# ADC_Block.net
KiCad netlist of a schematic drawn in Altium Designer
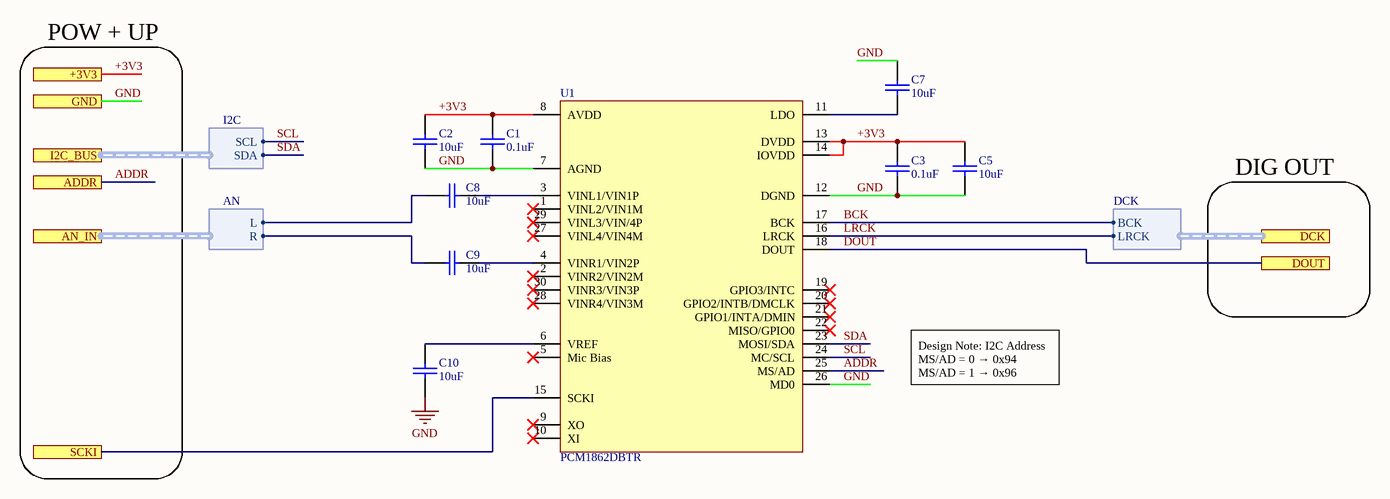
[diagram p0: ADC_Block.SchDoc]

(export (version "E")
  (design (tool "Eeschema 10.0.6"))
  (components
    (comp (ref "C1")
      (value "0.1uF")
      (footprint "0402-CAP-TDK")
      (fields (field (name "JLCPART") "C307331"))
      (libsource (lib "LIB2022 - Passives") (part "CAP-SMD"))
    )
    (comp (ref "C2")
      (value "10uF")
      (footprint "0603-CAP-TDK")
      (fields (field (name "JLCPART") "C96446"))
      (libsource (lib "LIB2022 - Passives") (part "CAP-SMD"))
    )
    (comp (ref "C3")
      (value "0.1uF")
      (footprint "0402-CAP-TDK")
      (fields (field (name "JLCPART") "C307331"))
      (libsource (lib "LIB2022 - Passives") (part "CAP-SMD"))
    )
    (comp (ref "C5")
      (value "10uF")
      (footprint "0603-CAP-TDK")
      (fields (field (name "JLCPART") "C96446"))
      (libsource (lib "LIB2022 - Passives") (part "CAP-SMD"))
    )
    (comp (ref "C7")
      (value "10uF")
      (footprint "0603-CAP-TDK")
      (fields (field (name "JLCPART") "C96446"))
      (libsource (lib "LIB2022 - Passives") (part "CAP-SMD"))
    )
    (comp (ref "C8")
      (value "10uF")
      (footprint "0603-CAP-TDK")
      (fields (field (name "JLCPART") "C96446"))
      (libsource (lib "LIB2022 - Passives") (part "CAP-SMD"))
    )
    (comp (ref "C9")
      (value "10uF")
      (footprint "0603-CAP-TDK")
      (fields (field (name "JLCPART") "C96446"))
      (libsource (lib "LIB2022 - Passives") (part "CAP-SMD"))
    )
    (comp (ref "C10")
      (value "10uF")
      (footprint "0603-CAP-TDK")
      (fields (field (name "JLCPART") "C96446"))
      (libsource (lib "LIB2022 - Passives") (part "CAP-SMD"))
    )
    (comp (ref "U1")
      (value "PCM1862DBTR")
      (footprint "TI-TSSOP-30-DBT0030A")
      (fields (field (name "JLCPART") "C544647"))
      (libsource (lib "LIB2022 - ICs") (part "PCM1862DBTR"))
    )
  )
  (nets
    (net (code "4") (name "/+3V3") (class "Default")
      (node (ref "C1") (pin "2") (pinfunction "2_2") (pintype "passive"))
      (node (ref "C2") (pin "2") (pinfunction "2_2") (pintype "passive"))
      (node (ref "C3") (pin "2") (pinfunction "2_2") (pintype "passive"))
      (node (ref "C5") (pin "2") (pinfunction "2_2") (pintype "passive"))
      (node (ref "U1") (pin "13") (pinfunction "DVDD_13") (pintype "passive"))
      (node (ref "U1") (pin "14") (pinfunction "IOVDD_14") (pintype "passive"))
      (node (ref "U1") (pin "8") (pinfunction "AVDD_8") (pintype "passive"))
    )
    (net (code "5") (name "/ADDR") (class "Default")
      (node (ref "U1") (pin "25") (pinfunction "MS/AD_25") (pintype "passive"))
    )
    (net (code "6") (name "/BCK") (class "Default")
      (node (ref "U1") (pin "17") (pinfunction "BCK_17") (pintype "passive"))
    )
    (net (code "7") (name "/DOUT") (class "Default")
      (node (ref "U1") (pin "18") (pinfunction "DOUT_18") (pintype "passive"))
    )
    (net (code "8") (name "/L") (class "Default")
      (node (ref "C8") (pin "2") (pinfunction "2_2") (pintype "passive"))
    )
    (net (code "9") (name "/LRCK") (class "Default")
      (node (ref "U1") (pin "16") (pinfunction "LRCK_16") (pintype "passive"))
    )
    (net (code "10") (name "/R") (class "Default")
      (node (ref "C9") (pin "2") (pinfunction "2_2") (pintype "passive"))
    )
    (net (code "11") (name "/SCKI") (class "Default")
      (node (ref "U1") (pin "15") (pinfunction "SCKI_15") (pintype "passive"))
    )
    (net (code "12") (name "/SCL") (class "Default")
      (node (ref "U1") (pin "24") (pinfunction "MC/SCL_24") (pintype "passive"))
    )
    (net (code "13") (name "/SDA") (class "Default")
      (node (ref "U1") (pin "23") (pinfunction "MOSI/SDA_23") (pintype "passive"))
    )
    (net (code "17") (name "GND") (class "Default")
      (node (ref "C1") (pin "1") (pinfunction "1_1") (pintype "passive"))
      (node (ref "C10") (pin "1") (pinfunction "1_1") (pintype "passive"))
      (node (ref "C2") (pin "1") (pinfunction "1_1") (pintype "passive"))
      (node (ref "C3") (pin "1") (pinfunction "1_1") (pintype "passive"))
      (node (ref "C5") (pin "1") (pinfunction "1_1") (pintype "passive"))
      (node (ref "C7") (pin "2") (pinfunction "2_2") (pintype "passive"))
      (node (ref "U1") (pin "12") (pinfunction "DGND_12") (pintype "passive"))
      (node (ref "U1") (pin "26") (pinfunction "MD0_26") (pintype "passive"))
      (node (ref "U1") (pin "7") (pinfunction "AGND_7") (pintype "passive"))
    )
    (net (code "18") (name "Net-(U1-LDO)") (class "Default")
      (node (ref "C7") (pin "1") (pinfunction "1_1") (pintype "passive"))
      (node (ref "U1") (pin "11") (pinfunction "LDO_11") (pintype "passive"))
    )
    (net (code "19") (name "Net-(U1-VINL1{slash}VIN1P)") (class "Default")
      (node (ref "C8") (pin "1") (pinfunction "1_1") (pintype "passive"))
      (node (ref "U1") (pin "3") (pinfunction "VINL1/VIN1P_3") (pintype "passive"))
    )
    (net (code "20") (name "Net-(U1-VINR1{slash}VIN2P)") (class "Default")
      (node (ref "C9") (pin "1") (pinfunction "1_1") (pintype "passive"))
      (node (ref "U1") (pin "4") (pinfunction "VINR1/VIN2P_4") (pintype "passive"))
    )
    (net (code "21") (name "Net-(U1-VREF)") (class "Default")
      (node (ref "C10") (pin "2") (pinfunction "2_2") (pintype "passive"))
      (node (ref "U1") (pin "6") (pinfunction "VREF_6") (pintype "passive"))
    )
    (net (code "22") (name "unconnected-(U1-GPIO1{slash}INTA{slash}DMIN-Pad21)") (class "Default")
      (node (ref "U1") (pin "21") (pinfunction "GPIO1/INTA/DMIN_21") (pintype "passive+no_connect"))
    )
    (net (code "23") (name "unconnected-(U1-GPIO2{slash}INTB{slash}DMCLK-Pad20)") (class "Default")
      (node (ref "U1") (pin "20") (pinfunction "GPIO2/INTB/DMCLK_20") (pintype "passive+no_connect"))
    )
    (net (code "24") (name "unconnected-(U1-GPIO3{slash}INTC-Pad19)") (class "Default")
      (node (ref "U1") (pin "19") (pinfunction "GPIO3/INTC_19") (pintype "passive+no_connect"))
    )
    (net (code "25") (name "unconnected-(U1-MISO{slash}GPIO0-Pad22)") (class "Default")
      (node (ref "U1") (pin "22") (pinfunction "MISO/GPIO0_22") (pintype "passive+no_connect"))
    )
    (net (code "26") (name "unconnected-(U1-Mic_Bias-Pad5)") (class "Default")
      (node (ref "U1") (pin "5") (pinfunction "Mic_Bias_5") (pintype "passive+no_connect"))
    )
    (net (code "27") (name "unconnected-(U1-VINL2{slash}VIN1M-Pad1)") (class "Default")
      (node (ref "U1") (pin "1") (pinfunction "VINL2/VIN1M_1") (pintype "passive+no_connect"))
    )
    (net (code "28") (name "unconnected-(U1-VINL3{slash}VIN{slash}4P-Pad29)") (class "Default")
      (node (ref "U1") (pin "29") (pinfunction "VINL3/VIN/4P_29") (pintype "passive+no_connect"))
    )
    (net (code "29") (name "unconnected-(U1-VINL4{slash}VIN4M-Pad27)") (class "Default")
      (node (ref "U1") (pin "27") (pinfunction "VINL4/VIN4M_27") (pintype "passive+no_connect"))
    )
    (net (code "30") (name "unconnected-(U1-VINR2{slash}VIN2M-Pad2)") (class "Default")
      (node (ref "U1") (pin "2") (pinfunction "VINR2/VIN2M_2") (pintype "passive+no_connect"))
    )
    (net (code "31") (name "unconnected-(U1-VINR3{slash}VIN3P-Pad30)") (class "Default")
      (node (ref "U1") (pin "30") (pinfunction "VINR3/VIN3P_30") (pintype "passive+no_connect"))
    )
    (net (code "32") (name "unconnected-(U1-VINR4{slash}VIN3M-Pad28)") (class "Default")
      (node (ref "U1") (pin "28") (pinfunction "VINR4/VIN3M_28") (pintype "passive+no_connect"))
    )
    (net (code "33") (name "unconnected-(U1-XI-Pad10)") (class "Default")
      (node (ref "U1") (pin "10") (pinfunction "XI_10") (pintype "passive+no_connect"))
    )
    (net (code "34") (name "unconnected-(U1-XO-Pad9)") (class "Default")
      (node (ref "U1") (pin "9") (pinfunction "XO_9") (pintype "passive+no_connect"))
    )
  )
)
